# level_shifter.net
KiCad netlist of a schematic drawn in EAGLE
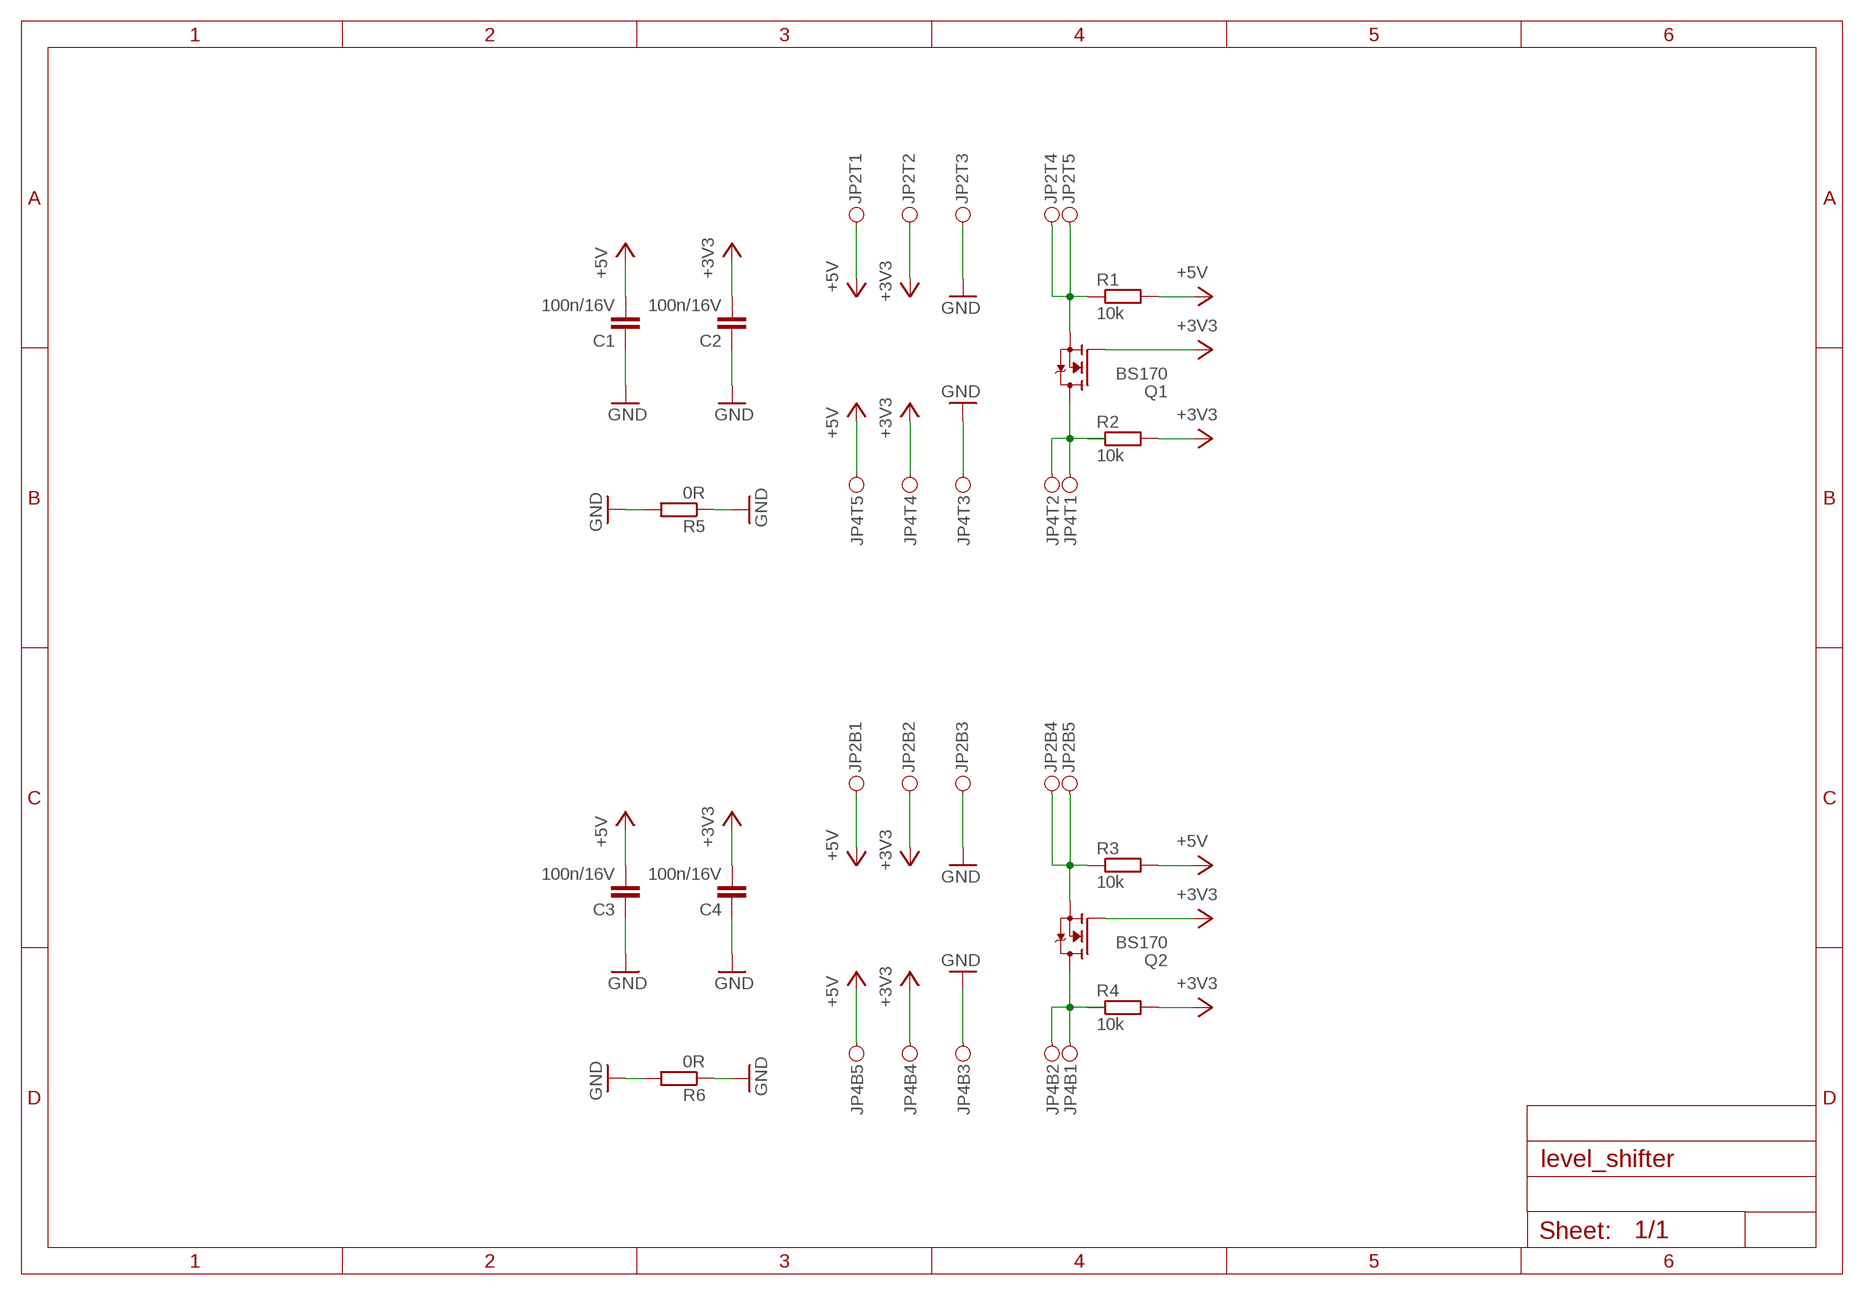
[diagram p0: schematic, sheet 1]

(export (version "E")
  (design (tool "Eeschema 10.0.6"))
  (components
    (comp (ref "C1")
      (value "100n/16V")
      (footprint "eagle-import:C0603S")
      (libsource (lib "eagle-import") (part "C-EUC0603S"))
    )
    (comp (ref "C2")
      (value "100n/16V")
      (footprint "eagle-import:C0603S")
      (libsource (lib "eagle-import") (part "C-EUC0603S"))
    )
    (comp (ref "C3")
      (value "100n/16V")
      (footprint "eagle-import:C0603S")
      (libsource (lib "eagle-import") (part "C-EUC0603S"))
    )
    (comp (ref "C4")
      (value "100n/16V")
      (footprint "eagle-import:C0603S")
      (libsource (lib "eagle-import") (part "C-EUC0603S"))
    )
    (comp (ref "JP2")
      (value "PINH2X05")
      (footprint "eagle-import:PINH2X05SMD")
      (libsource (lib "eagle-import") (part "PINH2X05"))
    )
    (comp (ref "JP4")
      (value "PINH2X05")
      (footprint "eagle-import:PINH2X05SMD")
      (libsource (lib "eagle-import") (part "PINH2X05"))
    )
    (comp (ref "Q1")
      (value "BS170")
      (footprint "eagle-import:SOT23_DIST")
      (libsource (lib "eagle-import") (part "N-MOSFET-SOT23-DIST"))
    )
    (comp (ref "Q2")
      (value "BS170")
      (footprint "eagle-import:SOT23")
      (libsource (lib "eagle-import") (part "N-MOSFET-SOT23-GSD"))
    )
    (comp (ref "R1")
      (value "10k")
      (footprint "eagle-import:R0603S")
      (libsource (lib "eagle-import") (part "R-EU_R0603S"))
    )
    (comp (ref "R2")
      (value "10k")
      (footprint "eagle-import:R0603S")
      (libsource (lib "eagle-import") (part "R-EU_R0603S"))
    )
    (comp (ref "R3")
      (value "10k")
      (footprint "eagle-import:R0603S")
      (libsource (lib "eagle-import") (part "R-EU_R0603S"))
    )
    (comp (ref "R4")
      (value "10k")
      (footprint "eagle-import:R0603S")
      (libsource (lib "eagle-import") (part "R-EU_R0603S"))
    )
    (comp (ref "R5")
      (value "0R")
      (footprint "eagle-import:R1206S")
      (libsource (lib "eagle-import") (part "R-EU_R1206S"))
    )
    (comp (ref "R6")
      (value "0R")
      (footprint "eagle-import:R1206S")
      (libsource (lib "eagle-import") (part "R-EU_R1206S"))
    )
  )
  (nets
    (net (code "1") (name "+3V3") (class "Default")
      (node (ref "C2") (pin "2") (pinfunction "2_2") (pintype "passive"))
      (node (ref "C4") (pin "2") (pinfunction "2_2") (pintype "passive"))
      (node (ref "JP2") (pin "B2") (pinfunction "1_B2") (pintype "passive"))
      (node (ref "JP2") (pin "T2") (pinfunction "1_T2") (pintype "passive"))
      (node (ref "JP4") (pin "B4") (pinfunction "1_B4") (pintype "passive"))
      (node (ref "JP4") (pin "T4") (pinfunction "1_T4") (pintype "passive"))
      (node (ref "Q1") (pin "1") (pinfunction "G_1") (pintype "passive"))
      (node (ref "Q2") (pin "1") (pinfunction "G_1") (pintype "passive"))
      (node (ref "R2") (pin "2") (pinfunction "2_2") (pintype "passive"))
      (node (ref "R4") (pin "2") (pinfunction "2_2") (pintype "passive"))
    )
    (net (code "2") (name "+5V") (class "Default")
      (node (ref "C1") (pin "2") (pinfunction "2_2") (pintype "passive"))
      (node (ref "C3") (pin "2") (pinfunction "2_2") (pintype "passive"))
      (node (ref "JP2") (pin "B1") (pinfunction "1_B1") (pintype "passive"))
      (node (ref "JP2") (pin "T1") (pinfunction "1_T1") (pintype "passive"))
      (node (ref "JP4") (pin "B5") (pinfunction "1_B5") (pintype "passive"))
      (node (ref "JP4") (pin "T5") (pinfunction "1_T5") (pintype "passive"))
      (node (ref "R1") (pin "2") (pinfunction "2_2") (pintype "passive"))
      (node (ref "R3") (pin "2") (pinfunction "2_2") (pintype "passive"))
    )
    (net (code "3") (name "GND") (class "Default")
      (node (ref "C1") (pin "1") (pinfunction "1_1") (pintype "passive"))
      (node (ref "C2") (pin "1") (pinfunction "1_1") (pintype "passive"))
      (node (ref "C3") (pin "1") (pinfunction "1_1") (pintype "passive"))
      (node (ref "C4") (pin "1") (pinfunction "1_1") (pintype "passive"))
      (node (ref "JP2") (pin "B3") (pinfunction "1_B3") (pintype "passive"))
      (node (ref "JP2") (pin "T3") (pinfunction "1_T3") (pintype "passive"))
      (node (ref "JP4") (pin "B3") (pinfunction "1_B3") (pintype "passive"))
      (node (ref "JP4") (pin "T3") (pinfunction "1_T3") (pintype "passive"))
      (node (ref "R5") (pin "1") (pinfunction "1_1") (pintype "passive"))
      (node (ref "R5") (pin "2") (pinfunction "2_2") (pintype "passive"))
      (node (ref "R6") (pin "1") (pinfunction "1_1") (pintype "passive"))
      (node (ref "R6") (pin "2") (pinfunction "2_2") (pintype "passive"))
    )
    (net (code "4") (name "Net-(JP2D-1)") (class "Default")
      (node (ref "JP2") (pin "B4") (pinfunction "1_B4") (pintype "passive"))
      (node (ref "JP2") (pin "B5") (pinfunction "1_B5") (pintype "passive"))
      (node (ref "Q2") (pin "2") (pinfunction "S_2") (pintype "passive"))
      (node (ref "R3") (pin "1") (pinfunction "1_1") (pintype "passive"))
    )
    (net (code "5") (name "Net-(JP2I-1)") (class "Default")
      (node (ref "JP2") (pin "T4") (pinfunction "1_T4") (pintype "passive"))
      (node (ref "JP2") (pin "T5") (pinfunction "1_T5") (pintype "passive"))
      (node (ref "Q1") (pin "2") (pinfunction "S_2") (pintype "passive"))
      (node (ref "R1") (pin "1") (pinfunction "1_1") (pintype "passive"))
    )
    (net (code "6") (name "Net-(JP4A-1)") (class "Default")
      (node (ref "JP4") (pin "B1") (pinfunction "1_B1") (pintype "passive"))
      (node (ref "JP4") (pin "B2") (pinfunction "1_B2") (pintype "passive"))
      (node (ref "Q2") (pin "3") (pinfunction "D_3") (pintype "passive"))
      (node (ref "R4") (pin "1") (pinfunction "1_1") (pintype "passive"))
    )
    (net (code "7") (name "Net-(JP4F-1)") (class "Default")
      (node (ref "JP4") (pin "T1") (pinfunction "1_T1") (pintype "passive"))
      (node (ref "JP4") (pin "T2") (pinfunction "1_T2") (pintype "passive"))
      (node (ref "Q1") (pin "3") (pinfunction "D_3") (pintype "passive"))
      (node (ref "R2") (pin "1") (pinfunction "1_1") (pintype "passive"))
    )
  )
)
